# LCD_BackPack.net
KiCad netlist of a schematic drawn in EAGLE
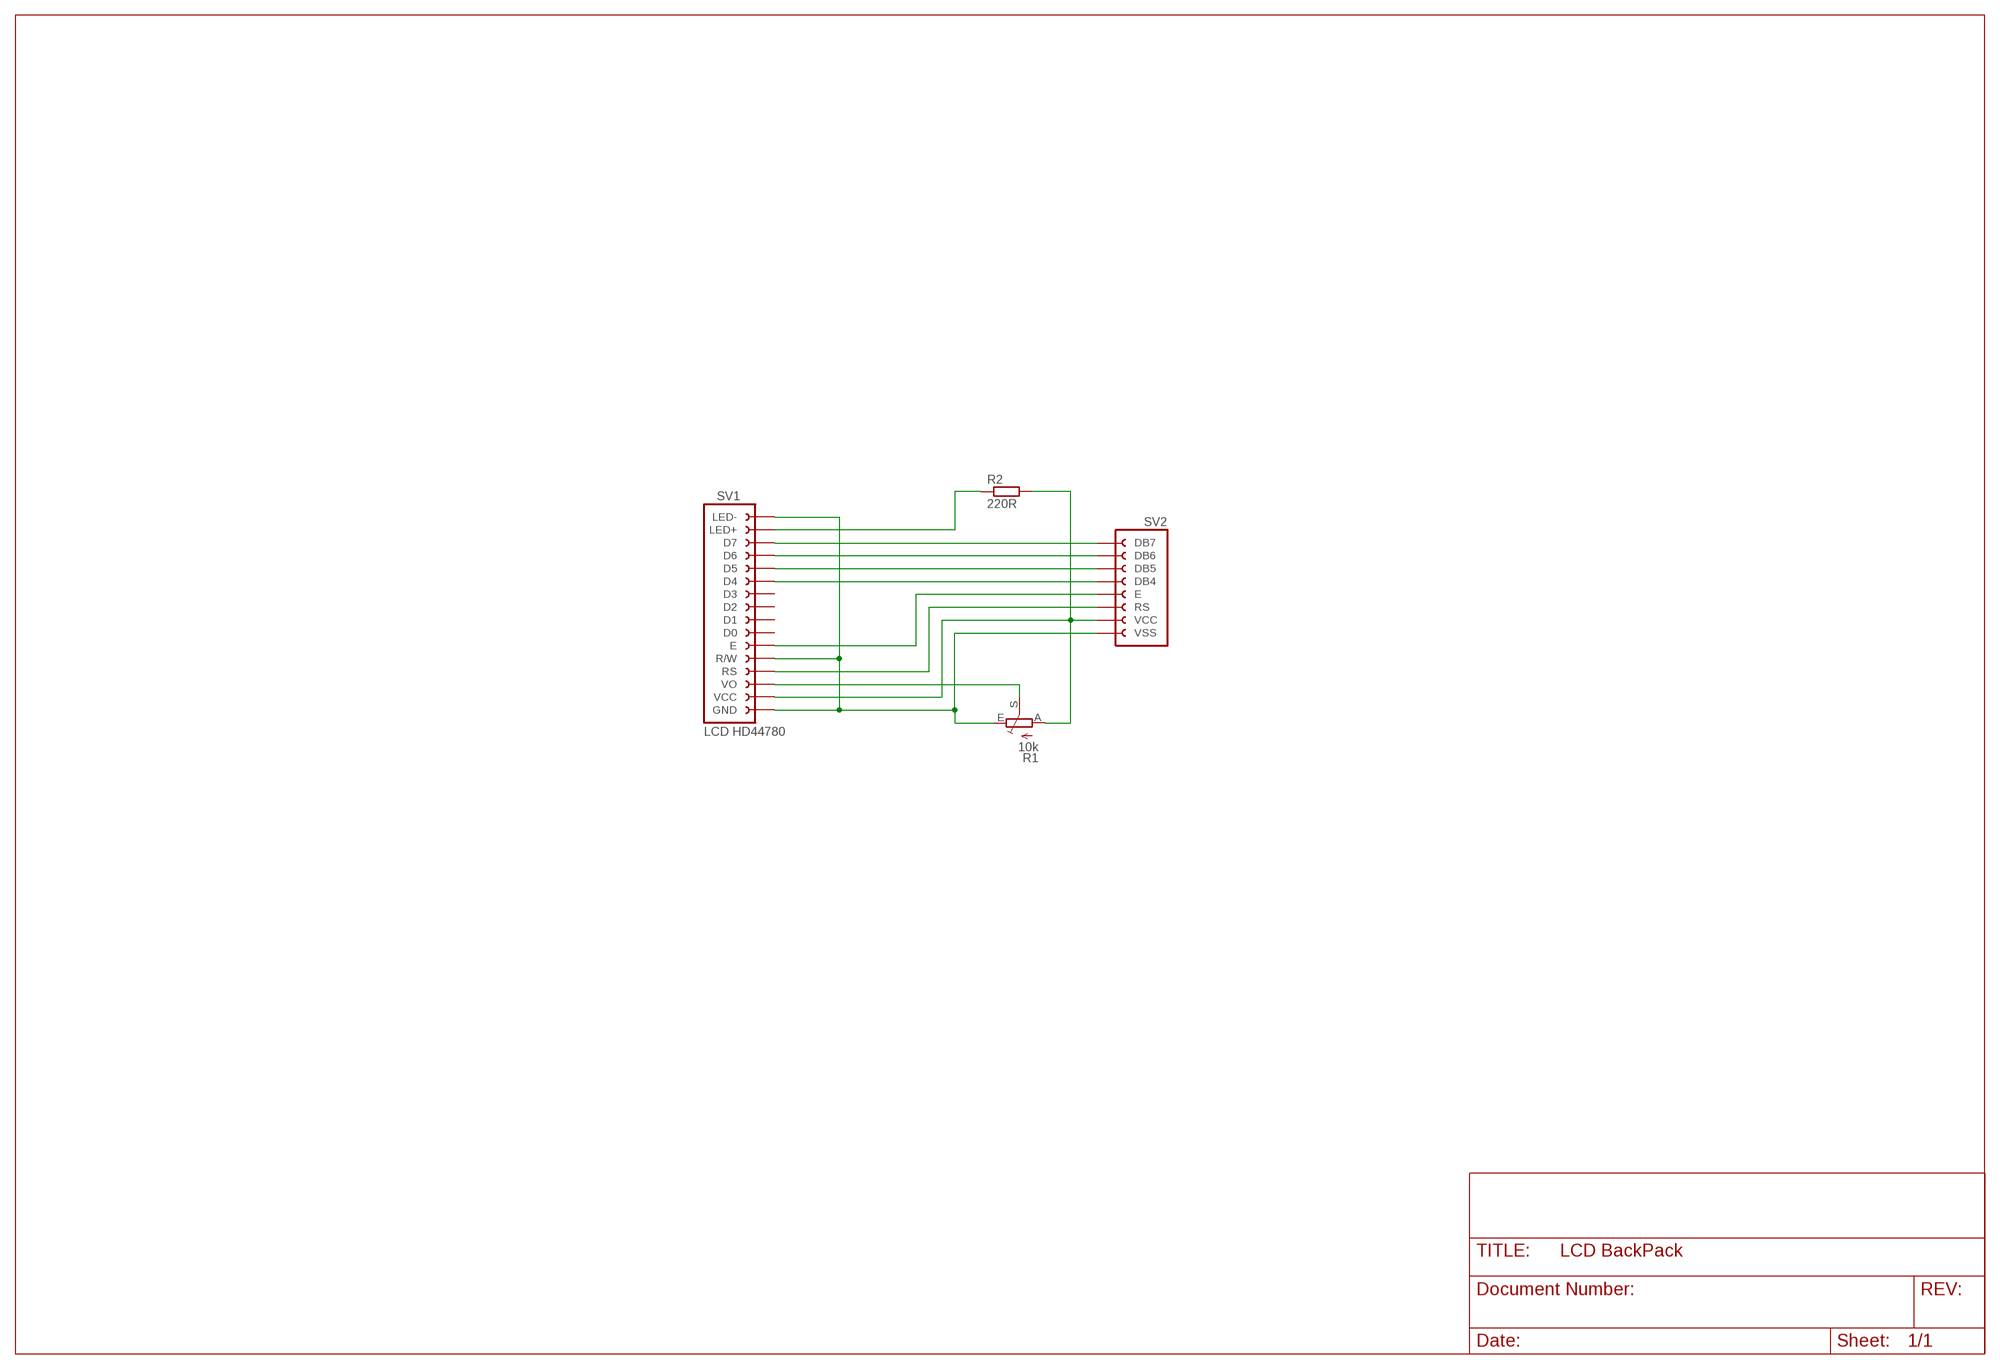
[diagram p0: schematic, sheet 1]

(export (version "E")
  (design (tool "Eeschema 10.0.6"))
  (components
    (comp (ref "R1")
      (value "10k")
      (footprint "eagle-import:CA6V")
      (libsource (lib "eagle-import") (part "POTENTIOMETER_CA6VCA6V"))
    )
    (comp (ref "R2")
      (value "220R")
      (footprint "eagle-import:0204_7")
      (libsource (lib "eagle-import") (part "R-EU_0204/7"))
    )
    (comp (ref "SV1")
      (value "LCD-HD44780-16-PIN_FEMALE_HEADER")
      (footprint "eagle-import:LCD-HD44780-16-PIN_FEMALE_HEADER")
      (libsource (lib "eagle-import") (part "LCD-HD44780-16-PIN_FEMALE_HEADER"))
    )
    (comp (ref "SV2")
      (value "LCD-CONTROL_8-PIN_FEMALE_HEADER")
      (footprint "eagle-import:LCD-CONTROL_8-PIN_FEMALE_HEADER")
      (libsource (lib "eagle-import") (part "LCD-CONTROL_8-PIN_FEMALE_HEADER"))
    )
  )
  (nets
    (net (code "1") (name "Net-(R1-PadA)") (class "Default")
      (node (ref "R1") (pin "A") (pinfunction "A_A") (pintype "passive"))
      (node (ref "R2") (pin "2") (pinfunction "2_2") (pintype "passive"))
      (node (ref "SV1") (pin "VCC") (pinfunction "VCC_VCC") (pintype "passive"))
      (node (ref "SV2") (pin "VCC") (pinfunction "VCC_VCC") (pintype "passive"))
    )
    (net (code "2") (name "Net-(R1-PadE)") (class "Default")
      (node (ref "R1") (pin "E") (pinfunction "E_E") (pintype "passive"))
      (node (ref "SV1") (pin "GND") (pinfunction "GND_GND") (pintype "passive"))
      (node (ref "SV1") (pin "LED-") (pinfunction "LED-_LED-") (pintype "passive"))
      (node (ref "SV1") (pin "R/W") (pinfunction "R/W_R/W") (pintype "passive"))
      (node (ref "SV2") (pin "VSS") (pinfunction "VSS_VSS") (pintype "passive"))
    )
    (net (code "3") (name "Net-(R1-PadS)") (class "Default")
      (node (ref "R1") (pin "S") (pinfunction "S_S") (pintype "passive"))
      (node (ref "SV1") (pin "VO") (pinfunction "VO_VO") (pintype "passive"))
    )
    (net (code "4") (name "Net-(R2-Pad1)") (class "Default")
      (node (ref "R2") (pin "1") (pinfunction "1_1") (pintype "passive"))
      (node (ref "SV1") (pin "LED+") (pinfunction "LED+_LED+") (pintype "passive"))
    )
    (net (code "5") (name "Net-(SV1-PadD4)") (class "Default")
      (node (ref "SV1") (pin "D4") (pinfunction "D4_D4") (pintype "passive"))
      (node (ref "SV2") (pin "DB4") (pinfunction "DB4_DB4") (pintype "passive"))
    )
    (net (code "6") (name "Net-(SV1-PadD5)") (class "Default")
      (node (ref "SV1") (pin "D5") (pinfunction "D5_D5") (pintype "passive"))
      (node (ref "SV2") (pin "DB5") (pinfunction "DB5_DB5") (pintype "passive"))
    )
    (net (code "7") (name "Net-(SV1-PadD6)") (class "Default")
      (node (ref "SV1") (pin "D6") (pinfunction "D6_D6") (pintype "passive"))
      (node (ref "SV2") (pin "DB6") (pinfunction "DB6_DB6") (pintype "passive"))
    )
    (net (code "8") (name "Net-(SV1-PadD7)") (class "Default")
      (node (ref "SV1") (pin "D7") (pinfunction "D7_D7") (pintype "passive"))
      (node (ref "SV2") (pin "DB7") (pinfunction "DB7_DB7") (pintype "passive"))
    )
    (net (code "9") (name "Net-(SV1-PadE)") (class "Default")
      (node (ref "SV1") (pin "E") (pinfunction "E_E") (pintype "passive"))
      (node (ref "SV2") (pin "E") (pinfunction "E_E") (pintype "passive"))
    )
    (net (code "10") (name "Net-(SV1-PadRS)") (class "Default")
      (node (ref "SV1") (pin "RS") (pinfunction "RS_RS") (pintype "passive"))
      (node (ref "SV2") (pin "RS") (pinfunction "RS_RS") (pintype "passive"))
    )
    (net (code "11") (name "unconnected-(SV1-PadD0)") (class "Default")
      (node (ref "SV1") (pin "D0") (pinfunction "D0_D0") (pintype "passive"))
    )
    (net (code "12") (name "unconnected-(SV1-PadD1)") (class "Default")
      (node (ref "SV1") (pin "D1") (pinfunction "D1_D1") (pintype "passive"))
    )
    (net (code "13") (name "unconnected-(SV1-PadD2)") (class "Default")
      (node (ref "SV1") (pin "D2") (pinfunction "D2_D2") (pintype "passive"))
    )
    (net (code "14") (name "unconnected-(SV1-PadD3)") (class "Default")
      (node (ref "SV1") (pin "D3") (pinfunction "D3_D3") (pintype "passive"))
    )
  )
)
